# zLineIn_v_0_3a.net
KiCad netlist of a schematic drawn in EAGLE
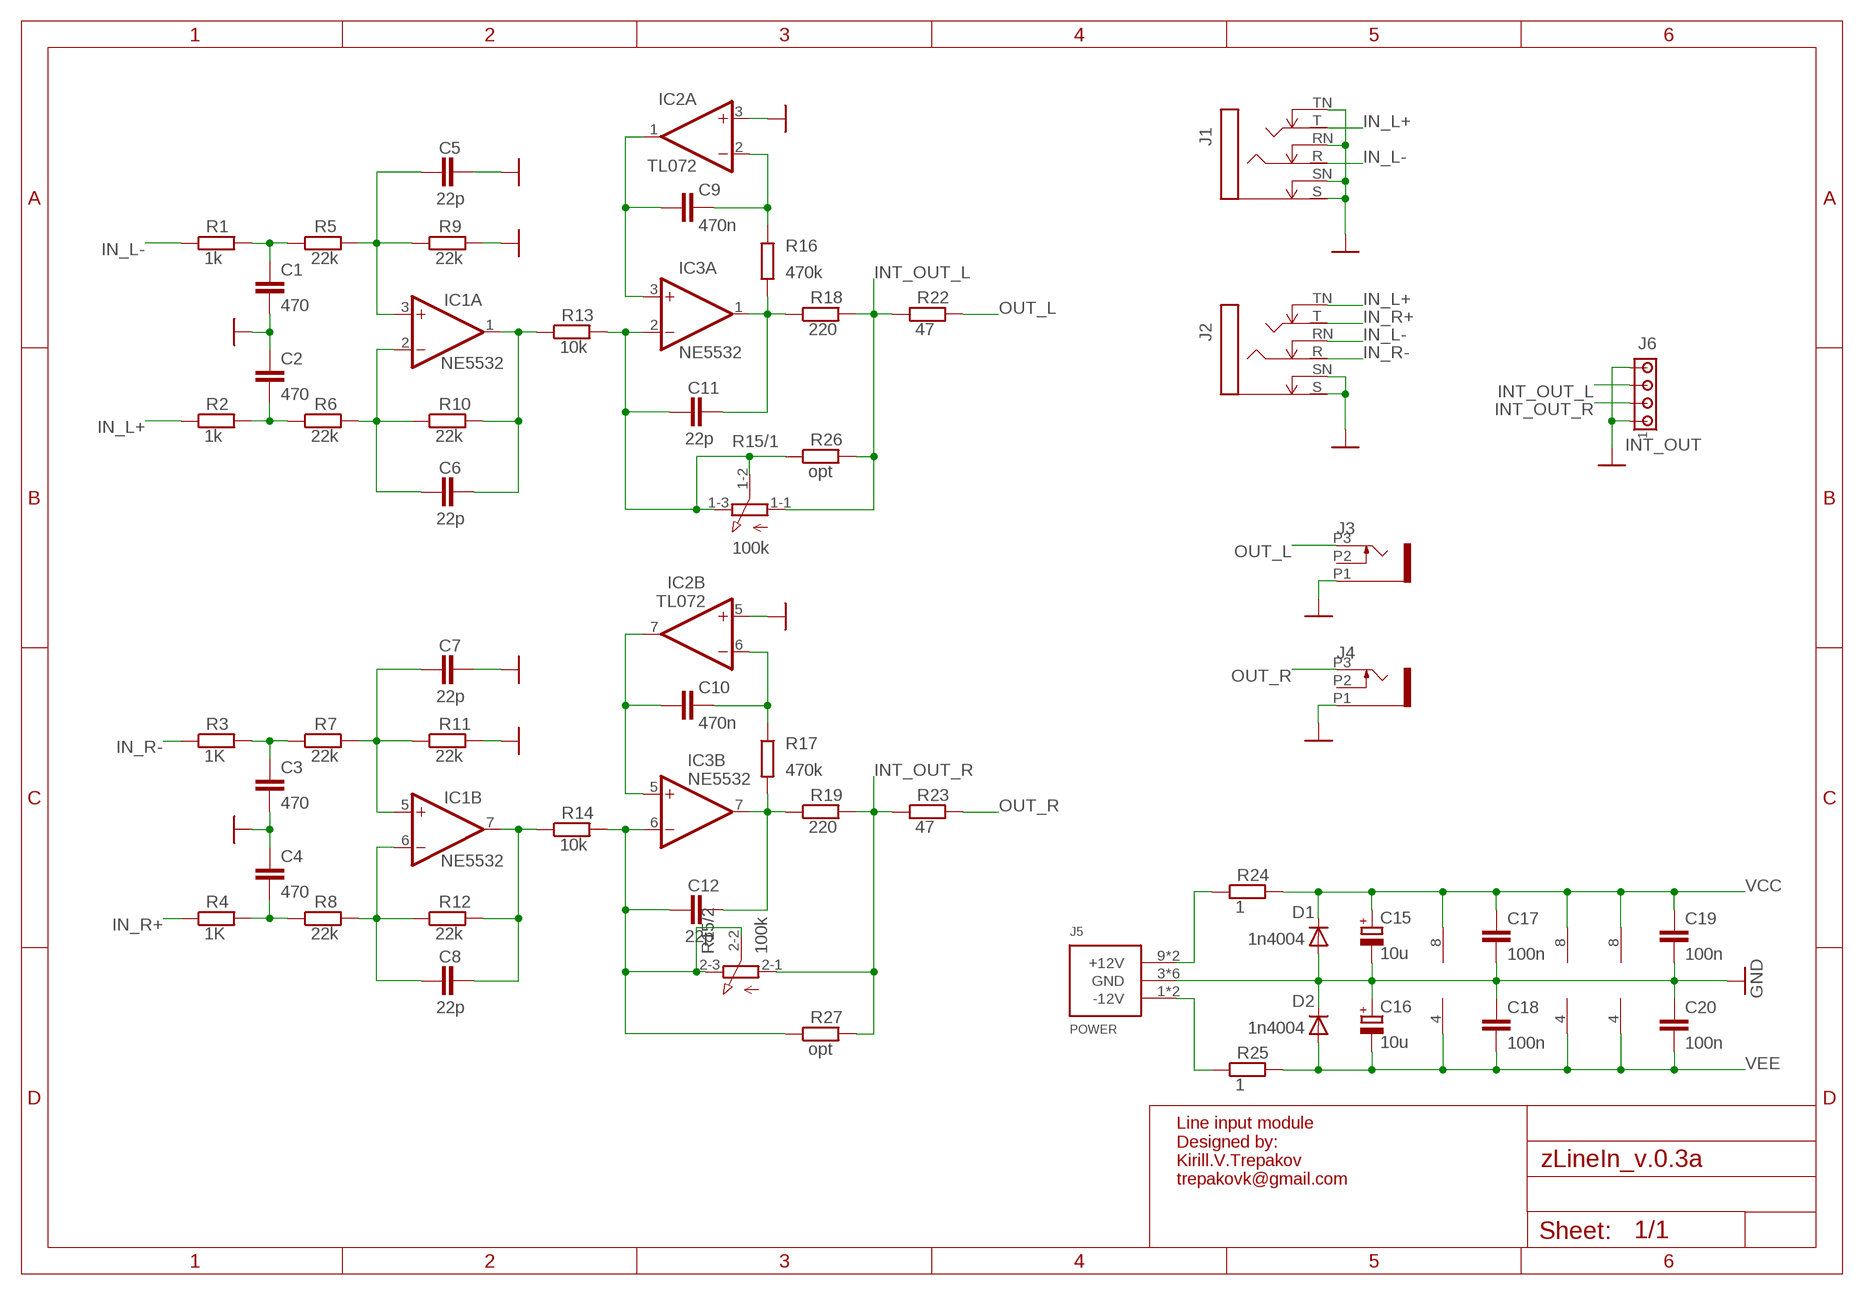
[diagram p0: schematic, sheet 1]

(export (version "E")
  (design (tool "Eeschema 10.0.6"))
  (components
    (comp (ref "C1")
      (value "470")
      (footprint "eagle-import:C050-024X044")
      (libsource (lib "eagle-import") (part "C-EU050-024X044"))
    )
    (comp (ref "C2")
      (value "470")
      (footprint "eagle-import:C050-024X044")
      (libsource (lib "eagle-import") (part "C-EU050-024X044"))
    )
    (comp (ref "C3")
      (value "470")
      (footprint "eagle-import:C050-024X044")
      (libsource (lib "eagle-import") (part "C-EU050-024X044"))
    )
    (comp (ref "C4")
      (value "470")
      (footprint "eagle-import:C050-024X044")
      (libsource (lib "eagle-import") (part "C-EU050-024X044"))
    )
    (comp (ref "C5")
      (value "22p")
      (footprint "eagle-import:C050-024X044")
      (libsource (lib "eagle-import") (part "C-EU050-024X044"))
    )
    (comp (ref "C6")
      (value "22p")
      (footprint "eagle-import:C050-024X044")
      (libsource (lib "eagle-import") (part "C-EU050-024X044"))
    )
    (comp (ref "C7")
      (value "22p")
      (footprint "eagle-import:C050-024X044")
      (libsource (lib "eagle-import") (part "C-EU050-024X044"))
    )
    (comp (ref "C8")
      (value "22p")
      (footprint "eagle-import:C050-024X044")
      (libsource (lib "eagle-import") (part "C-EU050-024X044"))
    )
    (comp (ref "C9")
      (value "470n")
      (footprint "eagle-import:C075-032X103")
      (libsource (lib "eagle-import") (part "C-EU075-032X103"))
    )
    (comp (ref "C10")
      (value "470n")
      (footprint "eagle-import:C075-032X103")
      (libsource (lib "eagle-import") (part "C-EU075-032X103"))
    )
    (comp (ref "C11")
      (value "22p")
      (footprint "eagle-import:C050-024X044")
      (libsource (lib "eagle-import") (part "C-EU050-024X044"))
    )
    (comp (ref "C12")
      (value "22p")
      (footprint "eagle-import:C050-024X044")
      (libsource (lib "eagle-import") (part "C-EU050-024X044"))
    )
    (comp (ref "C15")
      (value "10u")
      (footprint "eagle-import:E2,5-5")
      (libsource (lib "eagle-import") (part "CPOL-EUE2.5-5"))
    )
    (comp (ref "C16")
      (value "10u")
      (footprint "eagle-import:E2,5-5")
      (libsource (lib "eagle-import") (part "CPOL-EUE2.5-5"))
    )
    (comp (ref "C17")
      (value "100n")
      (footprint "eagle-import:C050-024X044")
      (libsource (lib "eagle-import") (part "C-EU050-024X044"))
    )
    (comp (ref "C18")
      (value "100n")
      (footprint "eagle-import:C050-024X044")
      (libsource (lib "eagle-import") (part "C-EU050-024X044"))
    )
    (comp (ref "C19")
      (value "100n")
      (footprint "eagle-import:C050-024X044")
      (libsource (lib "eagle-import") (part "C-EU050-024X044"))
    )
    (comp (ref "C20")
      (value "100n")
      (footprint "eagle-import:C050-024X044")
      (libsource (lib "eagle-import") (part "C-EU050-024X044"))
    )
    (comp (ref "D1")
      (value "1n4004")
      (footprint "eagle-import:DO41-7.6")
      (libsource (lib "eagle-import") (part "1N4004{dblquote}"))
    )
    (comp (ref "D2")
      (value "1n4004")
      (footprint "eagle-import:DO41-7.6")
      (libsource (lib "eagle-import") (part "1N4004{dblquote}"))
    )
    (comp (ref "IC1")
      (value "NE5532")
      (footprint "eagle-import:DIL08_")
      (libsource (lib "eagle-import") (part "TL072P_"))
    )
    (comp (ref "IC2")
      (value "TL072")
      (footprint "eagle-import:DIL08_")
      (libsource (lib "eagle-import") (part "TL072P_"))
    )
    (comp (ref "IC3")
      (value "NE5532")
      (footprint "eagle-import:DIL08_")
      (libsource (lib "eagle-import") (part "TL072P_"))
    )
    (comp (ref "J1")
      (value "IN_L")
      (footprint "eagle-import:NMJ6HC-S")
      (libsource (lib "eagle-import") (part "STEREOSW1"))
    )
    (comp (ref "J2")
      (value "IN_R")
      (footprint "eagle-import:NMJ6HC-S")
      (libsource (lib "eagle-import") (part "STEREOSW1"))
    )
    (comp (ref "J3")
      (value "WQP-PJ302M_JACK")
      (footprint "eagle-import:WQP-PJ302M_JACK")
      (libsource (lib "eagle-import") (part "WQP-PJ302M_JACK"))
    )
    (comp (ref "J4")
      (value "WQP-PJ302M_JACK")
      (footprint "eagle-import:WQP-PJ302M_JACK")
      (libsource (lib "eagle-import") (part "WQP-PJ302M_JACK"))
    )
    (comp (ref "J5")
      (value "POWER")
      (footprint "eagle-import:POWER_10")
      (libsource (lib "eagle-import") (part "POWER_SIMPLE10"))
    )
    (comp (ref "J6")
      (value "INT_OUT")
      (footprint "eagle-import:10X04MTA")
      (libsource (lib "eagle-import") (part "MTA04-100"))
    )
    (comp (ref "R1")
      (value "1k")
      (footprint "eagle-import:0204_7")
      (libsource (lib "eagle-import") (part "R-EU_0204/7"))
    )
    (comp (ref "R2")
      (value "1k")
      (footprint "eagle-import:0204_7")
      (libsource (lib "eagle-import") (part "R-EU_0204/7"))
    )
    (comp (ref "R3")
      (value "1K")
      (footprint "eagle-import:0204_7")
      (libsource (lib "eagle-import") (part "R-EU_0204/7"))
    )
    (comp (ref "R4")
      (value "1K")
      (footprint "eagle-import:0204_7")
      (libsource (lib "eagle-import") (part "R-EU_0204/7"))
    )
    (comp (ref "R5")
      (value "22k")
      (footprint "eagle-import:0204_7")
      (libsource (lib "eagle-import") (part "R-EU_0204/7"))
    )
    (comp (ref "R6")
      (value "22k")
      (footprint "eagle-import:0204_7")
      (libsource (lib "eagle-import") (part "R-EU_0204/7"))
    )
    (comp (ref "R7")
      (value "22k")
      (footprint "eagle-import:0204_7")
      (libsource (lib "eagle-import") (part "R-EU_0204/7"))
    )
    (comp (ref "R8")
      (value "22k")
      (footprint "eagle-import:0204_7")
      (libsource (lib "eagle-import") (part "R-EU_0204/7"))
    )
    (comp (ref "R9")
      (value "22k")
      (footprint "eagle-import:0204_7")
      (libsource (lib "eagle-import") (part "R-EU_0204/7"))
    )
    (comp (ref "R10")
      (value "22k")
      (footprint "eagle-import:0204_7")
      (libsource (lib "eagle-import") (part "R-EU_0204/7"))
    )
    (comp (ref "R11")
      (value "22k")
      (footprint "eagle-import:0204_7")
      (libsource (lib "eagle-import") (part "R-EU_0204/7"))
    )
    (comp (ref "R12")
      (value "22k")
      (footprint "eagle-import:0204_7")
      (libsource (lib "eagle-import") (part "R-EU_0204/7"))
    )
    (comp (ref "R13")
      (value "10k")
      (footprint "eagle-import:0204_7")
      (libsource (lib "eagle-import") (part "R-EU_0204/7"))
    )
    (comp (ref "R14")
      (value "10k")
      (footprint "eagle-import:0204_7")
      (libsource (lib "eagle-import") (part "R-EU_0204/7"))
    )
    (comp (ref "R15")
      (value "100k")
      (footprint "eagle-import:3RP_1610G")
      (libsource (lib "eagle-import") (part "3RP/1610G"))
    )
    (comp (ref "R16")
      (value "470k")
      (footprint "eagle-import:0204_7")
      (libsource (lib "eagle-import") (part "R-EU_0204/7"))
    )
    (comp (ref "R17")
      (value "470k")
      (footprint "eagle-import:0204_7")
      (libsource (lib "eagle-import") (part "R-EU_0204/7"))
    )
    (comp (ref "R18")
      (value "220")
      (footprint "eagle-import:0204_7")
      (libsource (lib "eagle-import") (part "R-EU_0204/7"))
    )
    (comp (ref "R19")
      (value "220")
      (footprint "eagle-import:0204_7")
      (libsource (lib "eagle-import") (part "R-EU_0204/7"))
    )
    (comp (ref "R22")
      (value "47")
      (footprint "eagle-import:0204_7")
      (libsource (lib "eagle-import") (part "R-EU_0204/7"))
    )
    (comp (ref "R23")
      (value "47")
      (footprint "eagle-import:0204_7")
      (libsource (lib "eagle-import") (part "R-EU_0204/7"))
    )
    (comp (ref "R24")
      (value "1")
      (footprint "eagle-import:0204_7")
      (libsource (lib "eagle-import") (part "R-EU_0204/7"))
    )
    (comp (ref "R25")
      (value "1")
      (footprint "eagle-import:0204_7")
      (libsource (lib "eagle-import") (part "R-EU_0204/7"))
    )
    (comp (ref "R26")
      (value "opt")
      (footprint "eagle-import:0204_7")
      (libsource (lib "eagle-import") (part "R-EU_0204/7"))
    )
    (comp (ref "R27")
      (value "opt")
      (footprint "eagle-import:0204_7")
      (libsource (lib "eagle-import") (part "R-EU_0204/7"))
    )
  )
  (nets
    (net (code "1") (name "/INT_OUT_L") (class "Default")
      (node (ref "J6") (pin "3") (pinfunction "3_3") (pintype "passive"))
      (node (ref "R15") (pin "1-1") (pinfunction "1_1-1") (pintype "passive"))
      (node (ref "R18") (pin "2") (pinfunction "2_2") (pintype "passive"))
      (node (ref "R22") (pin "1") (pinfunction "1_1") (pintype "passive"))
      (node (ref "R26") (pin "2") (pinfunction "2_2") (pintype "passive"))
    )
    (net (code "2") (name "/INT_OUT_R") (class "Default")
      (node (ref "J6") (pin "2") (pinfunction "2_2") (pintype "passive"))
      (node (ref "R15") (pin "2-1") (pinfunction "1_2-1") (pintype "passive"))
      (node (ref "R19") (pin "2") (pinfunction "2_2") (pintype "passive"))
      (node (ref "R23") (pin "1") (pinfunction "1_1") (pintype "passive"))
      (node (ref "R27") (pin "2") (pinfunction "2_2") (pintype "passive"))
    )
    (net (code "3") (name "/IN_L+") (class "Default")
      (node (ref "J1") (pin "T") (pinfunction "T_T") (pintype "passive"))
      (node (ref "J2") (pin "TN") (pinfunction "TN_TN") (pintype "passive"))
      (node (ref "R2") (pin "1") (pinfunction "1_1") (pintype "passive"))
    )
    (net (code "4") (name "/IN_L-") (class "Default")
      (node (ref "J1") (pin "R") (pinfunction "R_R") (pintype "passive"))
      (node (ref "J2") (pin "RN") (pinfunction "RN_RN") (pintype "passive"))
      (node (ref "R1") (pin "1") (pinfunction "1_1") (pintype "passive"))
    )
    (net (code "5") (name "/IN_R+") (class "Default")
      (node (ref "J2") (pin "T") (pinfunction "T_T") (pintype "passive"))
      (node (ref "R4") (pin "1") (pinfunction "1_1") (pintype "passive"))
    )
    (net (code "6") (name "/IN_R-") (class "Default")
      (node (ref "J2") (pin "R") (pinfunction "R_R") (pintype "passive"))
      (node (ref "R3") (pin "1") (pinfunction "1_1") (pintype "passive"))
    )
    (net (code "7") (name "/OUT_L") (class "Default")
      (node (ref "J3") (pin "P3") (pinfunction "3_P3") (pintype "passive"))
      (node (ref "R22") (pin "2") (pinfunction "2_2") (pintype "passive"))
    )
    (net (code "8") (name "/OUT_R") (class "Default")
      (node (ref "J4") (pin "P3") (pinfunction "3_P3") (pintype "passive"))
      (node (ref "R23") (pin "2") (pinfunction "2_2") (pintype "passive"))
    )
    (net (code "9") (name "/VCC") (class "Default")
      (node (ref "C15") (pin "+") (pinfunction "+_+") (pintype "passive"))
      (node (ref "C17") (pin "1") (pinfunction "1_1") (pintype "passive"))
      (node (ref "C19") (pin "1") (pinfunction "1_1") (pintype "passive"))
      (node (ref "D1") (pin "C") (pinfunction "C_C") (pintype "passive"))
      (node (ref "IC1") (pin "8") (pinfunction "V+_8") (pintype "power_in"))
      (node (ref "IC2") (pin "8") (pinfunction "V+_8") (pintype "power_in"))
      (node (ref "IC3") (pin "8") (pinfunction "V+_8") (pintype "power_in"))
      (node (ref "R24") (pin "2") (pinfunction "2_2") (pintype "passive"))
    )
    (net (code "10") (name "/VEE") (class "Default")
      (node (ref "C16") (pin "-") (pinfunction "-_-") (pintype "passive"))
      (node (ref "C18") (pin "2") (pinfunction "2_2") (pintype "passive"))
      (node (ref "C20") (pin "2") (pinfunction "2_2") (pintype "passive"))
      (node (ref "D2") (pin "A") (pinfunction "A_A") (pintype "passive"))
      (node (ref "IC1") (pin "4") (pinfunction "V-_4") (pintype "power_in"))
      (node (ref "IC2") (pin "4") (pinfunction "V-_4") (pintype "power_in"))
      (node (ref "IC3") (pin "4") (pinfunction "V-_4") (pintype "power_in"))
      (node (ref "R25") (pin "2") (pinfunction "2_2") (pintype "passive"))
    )
    (net (code "11") (name "GND") (class "Default")
      (node (ref "C1") (pin "2") (pinfunction "2_2") (pintype "passive"))
      (node (ref "C15") (pin "-") (pinfunction "-_-") (pintype "passive"))
      (node (ref "C16") (pin "+") (pinfunction "+_+") (pintype "passive"))
      (node (ref "C17") (pin "2") (pinfunction "2_2") (pintype "passive"))
      (node (ref "C18") (pin "1") (pinfunction "1_1") (pintype "passive"))
      (node (ref "C19") (pin "2") (pinfunction "2_2") (pintype "passive"))
      (node (ref "C2") (pin "1") (pinfunction "1_1") (pintype "passive"))
      (node (ref "C20") (pin "1") (pinfunction "1_1") (pintype "passive"))
      (node (ref "C3") (pin "2") (pinfunction "2_2") (pintype "passive"))
      (node (ref "C4") (pin "1") (pinfunction "1_1") (pintype "passive"))
      (node (ref "C5") (pin "2") (pinfunction "2_2") (pintype "passive"))
      (node (ref "C7") (pin "2") (pinfunction "2_2") (pintype "passive"))
      (node (ref "D1") (pin "A") (pinfunction "A_A") (pintype "passive"))
      (node (ref "D2") (pin "C") (pinfunction "C_C") (pintype "passive"))
      (node (ref "IC2") (pin "3") (pinfunction "+IN_3") (pintype "input"))
      (node (ref "IC2") (pin "5") (pinfunction "+IN_5") (pintype "input"))
      (node (ref "J1") (pin "RN") (pinfunction "RN_RN") (pintype "passive"))
      (node (ref "J1") (pin "S") (pinfunction "S_S") (pintype "passive"))
      (node (ref "J1") (pin "SN") (pinfunction "SN_SN") (pintype "passive"))
      (node (ref "J1") (pin "TN") (pinfunction "TN_TN") (pintype "passive"))
      (node (ref "J2") (pin "S") (pinfunction "S_S") (pintype "passive"))
      (node (ref "J2") (pin "SN") (pinfunction "SN_SN") (pintype "passive"))
      (node (ref "J3") (pin "P1") (pinfunction "1_P1") (pintype "passive"))
      (node (ref "J4") (pin "P1") (pinfunction "1_P1") (pintype "passive"))
      (node (ref "J5") (pin "3") (pinfunction "GND_3") (pintype "bidirectional"))
      (node (ref "J5") (pin "4") (pinfunction "GND_4") (pintype "bidirectional"))
      (node (ref "J5") (pin "5") (pinfunction "GND_5") (pintype "bidirectional"))
      (node (ref "J5") (pin "6") (pinfunction "GND_6") (pintype "bidirectional"))
      (node (ref "J5") (pin "7") (pinfunction "GND_7") (pintype "bidirectional"))
      (node (ref "J5") (pin "8") (pinfunction "GND_8") (pintype "bidirectional"))
      (node (ref "J6") (pin "1") (pinfunction "1_1") (pintype "passive"))
      (node (ref "J6") (pin "4") (pinfunction "4_4") (pintype "passive"))
      (node (ref "R11") (pin "2") (pinfunction "2_2") (pintype "passive"))
      (node (ref "R9") (pin "2") (pinfunction "2_2") (pintype "passive"))
    )
    (net (code "12") (name "Net-(C1-Pad1)") (class "Default")
      (node (ref "C1") (pin "1") (pinfunction "1_1") (pintype "passive"))
      (node (ref "R1") (pin "2") (pinfunction "2_2") (pintype "passive"))
      (node (ref "R5") (pin "1") (pinfunction "1_1") (pintype "passive"))
    )
    (net (code "13") (name "Net-(C2-Pad2)") (class "Default")
      (node (ref "C2") (pin "2") (pinfunction "2_2") (pintype "passive"))
      (node (ref "R2") (pin "2") (pinfunction "2_2") (pintype "passive"))
      (node (ref "R6") (pin "1") (pinfunction "1_1") (pintype "passive"))
    )
    (net (code "14") (name "Net-(C3-Pad1)") (class "Default")
      (node (ref "C3") (pin "1") (pinfunction "1_1") (pintype "passive"))
      (node (ref "R3") (pin "2") (pinfunction "2_2") (pintype "passive"))
      (node (ref "R7") (pin "1") (pinfunction "1_1") (pintype "passive"))
    )
    (net (code "15") (name "Net-(C4-Pad2)") (class "Default")
      (node (ref "C4") (pin "2") (pinfunction "2_2") (pintype "passive"))
      (node (ref "R4") (pin "2") (pinfunction "2_2") (pintype "passive"))
      (node (ref "R8") (pin "1") (pinfunction "1_1") (pintype "passive"))
    )
    (net (code "16") (name "Net-(IC1A-+IN)") (class "Default")
      (node (ref "C5") (pin "1") (pinfunction "1_1") (pintype "passive"))
      (node (ref "IC1") (pin "3") (pinfunction "+IN_3") (pintype "input"))
      (node (ref "R5") (pin "2") (pinfunction "2_2") (pintype "passive"))
      (node (ref "R9") (pin "1") (pinfunction "1_1") (pintype "passive"))
    )
    (net (code "17") (name "Net-(IC1A--IN)") (class "Default")
      (node (ref "C6") (pin "1") (pinfunction "1_1") (pintype "passive"))
      (node (ref "IC1") (pin "2") (pinfunction "-IN_2") (pintype "input"))
      (node (ref "R10") (pin "1") (pinfunction "1_1") (pintype "passive"))
      (node (ref "R6") (pin "2") (pinfunction "2_2") (pintype "passive"))
    )
    (net (code "18") (name "Net-(IC1A-OUT)") (class "Default")
      (node (ref "C6") (pin "2") (pinfunction "2_2") (pintype "passive"))
      (node (ref "IC1") (pin "1") (pinfunction "OUT_1") (pintype "output"))
      (node (ref "R10") (pin "2") (pinfunction "2_2") (pintype "passive"))
      (node (ref "R13") (pin "1") (pinfunction "1_1") (pintype "passive"))
    )
    (net (code "19") (name "Net-(IC1B-+IN)") (class "Default")
      (node (ref "C7") (pin "1") (pinfunction "1_1") (pintype "passive"))
      (node (ref "IC1") (pin "5") (pinfunction "+IN_5") (pintype "input"))
      (node (ref "R11") (pin "1") (pinfunction "1_1") (pintype "passive"))
      (node (ref "R7") (pin "2") (pinfunction "2_2") (pintype "passive"))
    )
    (net (code "20") (name "Net-(IC1B--IN)") (class "Default")
      (node (ref "C8") (pin "1") (pinfunction "1_1") (pintype "passive"))
      (node (ref "IC1") (pin "6") (pinfunction "-IN_6") (pintype "input"))
      (node (ref "R12") (pin "1") (pinfunction "1_1") (pintype "passive"))
      (node (ref "R8") (pin "2") (pinfunction "2_2") (pintype "passive"))
    )
    (net (code "21") (name "Net-(IC1B-OUT)") (class "Default")
      (node (ref "C8") (pin "2") (pinfunction "2_2") (pintype "passive"))
      (node (ref "IC1") (pin "7") (pinfunction "OUT_7") (pintype "output"))
      (node (ref "R12") (pin "2") (pinfunction "2_2") (pintype "passive"))
      (node (ref "R14") (pin "1") (pinfunction "1_1") (pintype "passive"))
    )
    (net (code "22") (name "Net-(IC2A--IN)") (class "Default")
      (node (ref "C9") (pin "2") (pinfunction "2_2") (pintype "passive"))
      (node (ref "IC2") (pin "2") (pinfunction "-IN_2") (pintype "input"))
      (node (ref "R16") (pin "1") (pinfunction "1_1") (pintype "passive"))
    )
    (net (code "23") (name "Net-(IC2A-OUT)") (class "Default")
      (node (ref "C9") (pin "1") (pinfunction "1_1") (pintype "passive"))
      (node (ref "IC2") (pin "1") (pinfunction "OUT_1") (pintype "output"))
      (node (ref "IC3") (pin "3") (pinfunction "+IN_3") (pintype "input"))
    )
    (net (code "24") (name "Net-(IC2B--IN)") (class "Default")
      (node (ref "C10") (pin "2") (pinfunction "2_2") (pintype "passive"))
      (node (ref "IC2") (pin "6") (pinfunction "-IN_6") (pintype "input"))
      (node (ref "R17") (pin "1") (pinfunction "1_1") (pintype "passive"))
    )
    (net (code "25") (name "Net-(IC2B-OUT)") (class "Default")
      (node (ref "C10") (pin "1") (pinfunction "1_1") (pintype "passive"))
      (node (ref "IC2") (pin "7") (pinfunction "OUT_7") (pintype "output"))
      (node (ref "IC3") (pin "5") (pinfunction "+IN_5") (pintype "input"))
    )
    (net (code "26") (name "Net-(IC3A--IN)") (class "Default")
      (node (ref "C11") (pin "1") (pinfunction "1_1") (pintype "passive"))
      (node (ref "IC3") (pin "2") (pinfunction "-IN_2") (pintype "input"))
      (node (ref "R13") (pin "2") (pinfunction "2_2") (pintype "passive"))
      (node (ref "R15") (pin "1-2") (pinfunction "2_1-2") (pintype "passive"))
      (node (ref "R15") (pin "1-3") (pinfunction "3_1-3") (pintype "passive"))
      (node (ref "R26") (pin "1") (pinfunction "1_1") (pintype "passive"))
    )
    (net (code "27") (name "Net-(IC3A-OUT)") (class "Default")
      (node (ref "C11") (pin "2") (pinfunction "2_2") (pintype "passive"))
      (node (ref "IC3") (pin "1") (pinfunction "OUT_1") (pintype "output"))
      (node (ref "R16") (pin "2") (pinfunction "2_2") (pintype "passive"))
      (node (ref "R18") (pin "1") (pinfunction "1_1") (pintype "passive"))
    )
    (net (code "28") (name "Net-(IC3B--IN)") (class "Default")
      (node (ref "C12") (pin "1") (pinfunction "1_1") (pintype "passive"))
      (node (ref "IC3") (pin "6") (pinfunction "-IN_6") (pintype "input"))
      (node (ref "R14") (pin "2") (pinfunction "2_2") (pintype "passive"))
      (node (ref "R15") (pin "2-2") (pinfunction "2_2-2") (pintype "passive"))
      (node (ref "R15") (pin "2-3") (pinfunction "3_2-3") (pintype "passive"))
      (node (ref "R27") (pin "1") (pinfunction "1_1") (pintype "passive"))
    )
    (net (code "29") (name "Net-(IC3B-OUT)") (class "Default")
      (node (ref "C12") (pin "2") (pinfunction "2_2") (pintype "passive"))
      (node (ref "IC3") (pin "7") (pinfunction "OUT_7") (pintype "output"))
      (node (ref "R17") (pin "2") (pinfunction "2_2") (pintype "passive"))
      (node (ref "R19") (pin "1") (pinfunction "1_1") (pintype "passive"))
    )
    (net (code "30") (name "Net-(J5-+12V-Pad10)") (class "Default")
      (node (ref "J5") (pin "10") (pinfunction "+12V_10") (pintype "bidirectional"))
      (node (ref "J5") (pin "9") (pinfunction "+12V_9") (pintype "bidirectional"))
      (node (ref "R24") (pin "1") (pinfunction "1_1") (pintype "passive"))
    )
    (net (code "31") (name "Net-(J5--12V-Pad1)") (class "Default")
      (node (ref "J5") (pin "1") (pinfunction "-12V_1") (pintype "bidirectional"))
      (node (ref "J5") (pin "2") (pinfunction "-12V_2") (pintype "bidirectional"))
      (node (ref "R25") (pin "1") (pinfunction "1_1") (pintype "passive"))
    )
    (net (code "32") (name "unconnected-(J3-2-PadP2)") (class "Default")
      (node (ref "J3") (pin "P2") (pinfunction "2_P2") (pintype "passive"))
    )
    (net (code "33") (name "unconnected-(J4-2-PadP2)") (class "Default")
      (node (ref "J4") (pin "P2") (pinfunction "2_P2") (pintype "passive"))
    )
  )
)
